# project_mount_board.net
KiCad netlist of a schematic drawn in EAGLE
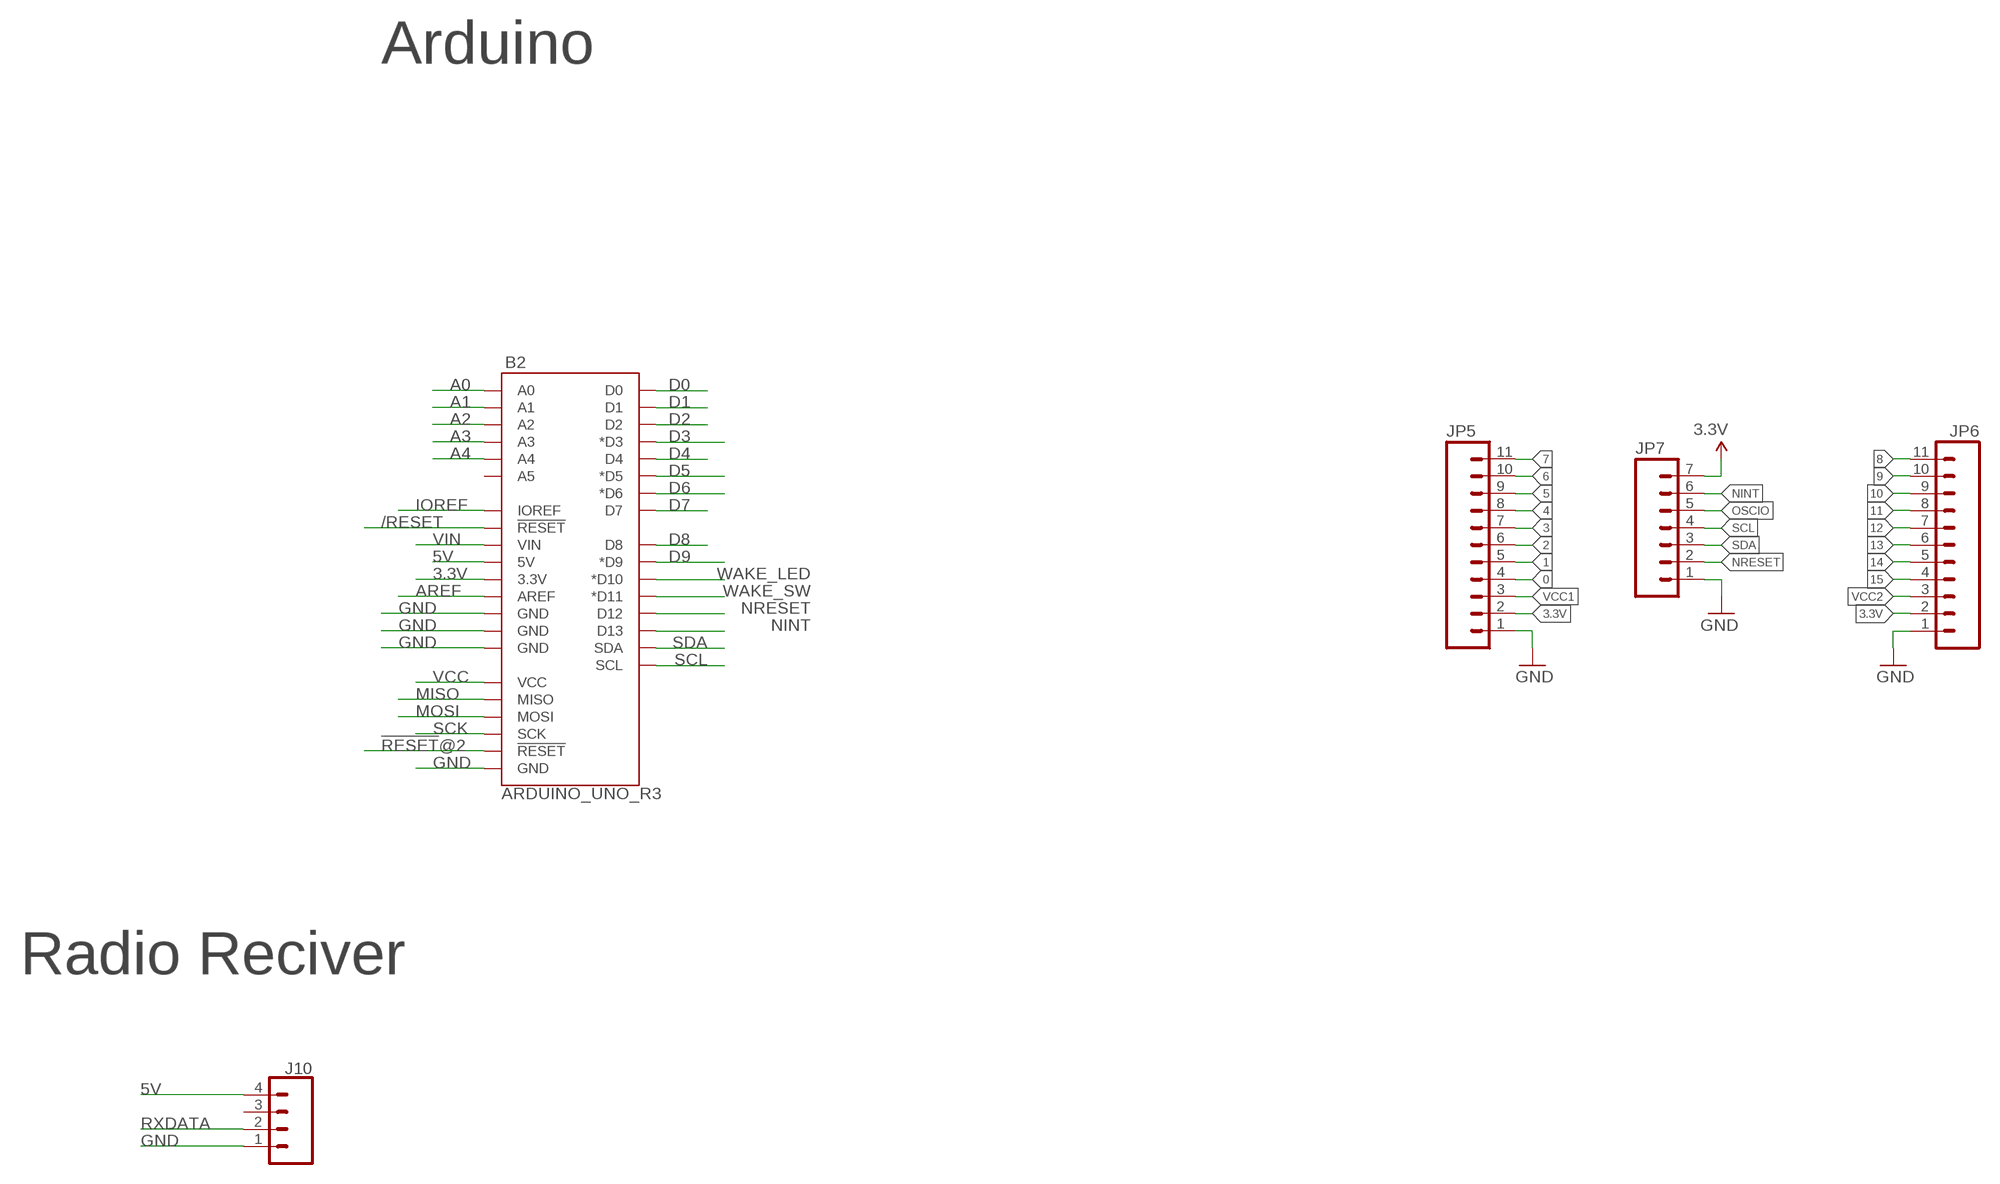
[diagram p0: schematic, sheet 1]

(export (version "E")
  (design (tool "Eeschema 10.0.6"))
  (components
    (comp (ref "B2")
      (value "ARDUINO_UNO_R3")
      (footprint "eagle-import:ARDUINO_R3")
      (libsource (lib "eagle-import") (part "ARDUINO_UNO_R3"))
    )
    (comp (ref "J10")
      (value "CONN_04")
      (footprint "eagle-import:1X04")
      (libsource (lib "eagle-import") (part "CONN_04"))
    )
    (comp (ref "JP5")
      (value "M111X11_NO_SILK")
      (footprint "eagle-import:1X11_NO_SILK")
      (libsource (lib "eagle-import") (part "M111X11_NO_SILK"))
    )
    (comp (ref "JP6")
      (value "M111X11_NO_SILK")
      (footprint "eagle-import:1X11_NO_SILK")
      (libsource (lib "eagle-import") (part "M111X11_NO_SILK"))
    )
    (comp (ref "JP7")
      (value "M07")
      (footprint "eagle-import:1X07")
      (libsource (lib "eagle-import") (part "M07"))
    )
  )
  (nets
    (net (code "1") (name "0") (class "Default")
      (node (ref "JP5") (pin "4") (pinfunction "4_4") (pintype "passive"))
    )
    (net (code "2") (name "1") (class "Default")
      (node (ref "JP5") (pin "5") (pinfunction "5_5") (pintype "passive"))
    )
    (net (code "3") (name "2") (class "Default")
      (node (ref "JP5") (pin "6") (pinfunction "6_6") (pintype "passive"))
    )
    (net (code "4") (name "3") (class "Default")
      (node (ref "JP5") (pin "7") (pinfunction "7_7") (pintype "passive"))
    )
    (net (code "5") (name "3.3V") (class "Default")
      (node (ref "B2") (pin "3.3V") (pinfunction "3.3V_3.3V") (pintype "bidirectional"))
      (node (ref "JP5") (pin "2") (pinfunction "2_2") (pintype "passive"))
      (node (ref "JP6") (pin "2") (pinfunction "2_2") (pintype "passive"))
      (node (ref "JP7") (pin "7") (pinfunction "7_7") (pintype "passive"))
    )
    (net (code "6") (name "4") (class "Default")
      (node (ref "JP5") (pin "8") (pinfunction "8_8") (pintype "passive"))
    )
    (net (code "7") (name "5") (class "Default")
      (node (ref "JP5") (pin "9") (pinfunction "9_9") (pintype "passive"))
    )
    (net (code "8") (name "5V") (class "Default")
      (node (ref "B2") (pin "5V") (pinfunction "5V_5V") (pintype "bidirectional"))
      (node (ref "J10") (pin "4") (pinfunction "4_4") (pintype "passive"))
    )
    (net (code "9") (name "6") (class "Default")
      (node (ref "JP5") (pin "10") (pinfunction "10_10") (pintype "passive"))
    )
    (net (code "10") (name "7") (class "Default")
      (node (ref "JP5") (pin "11") (pinfunction "11_11") (pintype "passive"))
    )
    (net (code "11") (name "8") (class "Default")
      (node (ref "JP6") (pin "11") (pinfunction "11_11") (pintype "passive"))
    )
    (net (code "12") (name "9") (class "Default")
      (node (ref "JP6") (pin "10") (pinfunction "10_10") (pintype "passive"))
    )
    (net (code "13") (name "10") (class "Default")
      (node (ref "JP6") (pin "9") (pinfunction "9_9") (pintype "passive"))
    )
    (net (code "14") (name "11") (class "Default")
      (node (ref "JP6") (pin "8") (pinfunction "8_8") (pintype "passive"))
    )
    (net (code "15") (name "12") (class "Default")
      (node (ref "JP6") (pin "7") (pinfunction "7_7") (pintype "passive"))
    )
    (net (code "16") (name "13") (class "Default")
      (node (ref "JP6") (pin "6") (pinfunction "6_6") (pintype "passive"))
    )
    (net (code "17") (name "14") (class "Default")
      (node (ref "JP6") (pin "5") (pinfunction "5_5") (pintype "passive"))
    )
    (net (code "18") (name "15") (class "Default")
      (node (ref "JP6") (pin "4") (pinfunction "4_4") (pintype "passive"))
    )
    (net (code "19") (name "A0") (class "Default")
      (node (ref "B2") (pin "A0") (pinfunction "A0_A0") (pintype "bidirectional"))
    )
    (net (code "20") (name "A1") (class "Default")
      (node (ref "B2") (pin "A1") (pinfunction "A1_A1") (pintype "bidirectional"))
    )
    (net (code "21") (name "A2") (class "Default")
      (node (ref "B2") (pin "A2") (pinfunction "A2_A2") (pintype "bidirectional"))
    )
    (net (code "22") (name "A3") (class "Default")
      (node (ref "B2") (pin "A3") (pinfunction "A3_A3") (pintype "bidirectional"))
    )
    (net (code "23") (name "A4") (class "Default")
      (node (ref "B2") (pin "A4") (pinfunction "A4_A4") (pintype "bidirectional"))
    )
    (net (code "24") (name "AREF") (class "Default")
      (node (ref "B2") (pin "AREF") (pinfunction "AREF_AREF") (pintype "bidirectional"))
    )
    (net (code "25") (name "D0") (class "Default")
      (node (ref "B2") (pin "D0") (pinfunction "D0_D0") (pintype "bidirectional"))
    )
    (net (code "26") (name "D1") (class "Default")
      (node (ref "B2") (pin "D1") (pinfunction "D1_D1") (pintype "bidirectional"))
    )
    (net (code "27") (name "D2") (class "Default")
      (node (ref "B2") (pin "D2") (pinfunction "D2_D2") (pintype "bidirectional"))
    )
    (net (code "28") (name "D3") (class "Default")
      (node (ref "B2") (pin "D3") (pinfunction "*D3_D3") (pintype "bidirectional"))
    )
    (net (code "29") (name "D4") (class "Default")
      (node (ref "B2") (pin "D4") (pinfunction "D4_D4") (pintype "bidirectional"))
    )
    (net (code "30") (name "D5") (class "Default")
      (node (ref "B2") (pin "D5") (pinfunction "*D5_D5") (pintype "bidirectional"))
    )
    (net (code "31") (name "D6") (class "Default")
      (node (ref "B2") (pin "D6") (pinfunction "*D6_D6") (pintype "bidirectional"))
    )
    (net (code "32") (name "D7") (class "Default")
      (node (ref "B2") (pin "D7") (pinfunction "D7_D7") (pintype "bidirectional"))
    )
    (net (code "33") (name "D8") (class "Default")
      (node (ref "B2") (pin "D8") (pinfunction "D8_D8") (pintype "bidirectional"))
    )
    (net (code "34") (name "D9") (class "Default")
      (node (ref "B2") (pin "D9") (pinfunction "*D9_D9") (pintype "bidirectional"))
    )
    (net (code "35") (name "GND") (class "Default")
      (node (ref "B2") (pin "GND@1") (pinfunction "GND_GND@1") (pintype "bidirectional"))
      (node (ref "B2") (pin "GND@2") (pinfunction "GND_GND@2") (pintype "bidirectional"))
      (node (ref "B2") (pin "GND@3") (pinfunction "GND_GND@3") (pintype "bidirectional"))
      (node (ref "B2") (pin "GND@4") (pinfunction "GND_GND@4") (pintype "bidirectional"))
      (node (ref "J10") (pin "1") (pinfunction "1_1") (pintype "passive"))
      (node (ref "JP5") (pin "1") (pinfunction "1_1") (pintype "passive"))
      (node (ref "JP6") (pin "1") (pinfunction "1_1") (pintype "passive"))
      (node (ref "JP7") (pin "1") (pinfunction "1_1") (pintype "passive"))
    )
    (net (code "36") (name "IOREF") (class "Default")
      (node (ref "B2") (pin "IOREF") (pinfunction "IOREF_IOREF") (pintype "bidirectional"))
    )
    (net (code "37") (name "MISO") (class "Default")
      (node (ref "B2") (pin "MISO") (pinfunction "MISO_MISO") (pintype "bidirectional"))
    )
    (net (code "38") (name "MOSI") (class "Default")
      (node (ref "B2") (pin "MOSI") (pinfunction "MOSI_MOSI") (pintype "bidirectional"))
    )
    (net (code "39") (name "NINT") (class "Default")
      (node (ref "B2") (pin "D13") (pinfunction "D13_D13") (pintype "bidirectional"))
      (node (ref "JP7") (pin "6") (pinfunction "6_6") (pintype "passive"))
    )
    (net (code "40") (name "NRESET") (class "Default")
      (node (ref "B2") (pin "D12") (pinfunction "D12_D12") (pintype "bidirectional"))
      (node (ref "JP7") (pin "2") (pinfunction "2_2") (pintype "passive"))
    )
    (net (code "41") (name "OSCIO") (class "Default")
      (node (ref "JP7") (pin "5") (pinfunction "5_5") (pintype "passive"))
    )
    (net (code "42") (name "RXDATA") (class "Default")
      (node (ref "J10") (pin "2") (pinfunction "2_2") (pintype "passive"))
    )
    (net (code "43") (name "SCK") (class "Default")
      (node (ref "B2") (pin "SCK") (pinfunction "SCK_SCK") (pintype "bidirectional"))
    )
    (net (code "44") (name "SCL") (class "Default")
      (node (ref "B2") (pin "SCL") (pinfunction "SCL_SCL") (pintype "bidirectional"))
      (node (ref "JP7") (pin "4") (pinfunction "4_4") (pintype "passive"))
    )
    (net (code "45") (name "SDA") (class "Default")
      (node (ref "B2") (pin "SDA") (pinfunction "SDA_SDA") (pintype "bidirectional"))
      (node (ref "JP7") (pin "3") (pinfunction "3_3") (pintype "passive"))
    )
    (net (code "46") (name "VCC") (class "Default")
      (node (ref "B2") (pin "VCC") (pinfunction "VCC_VCC") (pintype "bidirectional"))
    )
    (net (code "47") (name "VCC1") (class "Default")
      (node (ref "JP5") (pin "3") (pinfunction "3_3") (pintype "passive"))
    )
    (net (code "48") (name "VCC2") (class "Default")
      (node (ref "JP6") (pin "3") (pinfunction "3_3") (pintype "passive"))
    )
    (net (code "49") (name "VIN") (class "Default")
      (node (ref "B2") (pin "VIN") (pinfunction "VIN_VIN") (pintype "bidirectional"))
    )
    (net (code "50") (name "WAKE_LED") (class "Default")
      (node (ref "B2") (pin "D10") (pinfunction "*D10_D10") (pintype "bidirectional"))
    )
    (net (code "51") (name "WAKE_SW") (class "Default")
      (node (ref "B2") (pin "D11") (pinfunction "*D11_D11") (pintype "bidirectional"))
    )
    (net (code "52") (name "unconnected-(B2-PadA5)") (class "Default")
      (node (ref "B2") (pin "A5") (pinfunction "A5_A5") (pintype "bidirectional"))
    )
    (net (code "53") (name "unconnected-(J10-Pad3)") (class "Default")
      (node (ref "J10") (pin "3") (pinfunction "3_3") (pintype "passive"))
    )
    (net (code "54") (name "{slash}RESET") (class "Default")
      (node (ref "B2") (pin "RESET@1") (pinfunction "~{RESET}_RESET@1") (pintype "bidirectional"))
    )
    (net (code "55") (name "~{RESET}@2") (class "Default")
      (node (ref "B2") (pin "RESET@2") (pinfunction "~{RESET}_RESET@2") (pintype "bidirectional"))
    )
  )
)
